# 6_SENSORS.net
KiCad netlist of a schematic drawn in Altium Designer
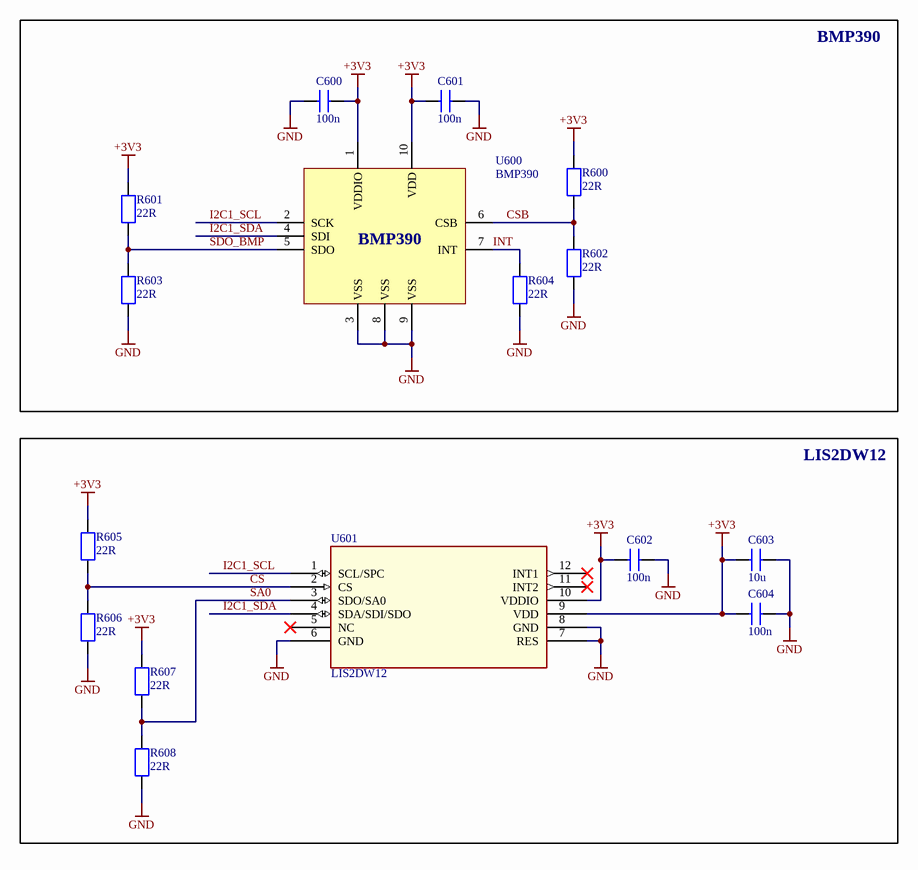
[diagram p0: [6] SENSORS.SchDoc]

(export (version "E")
  (design (tool "Eeschema 10.0.6"))
  (components
    (comp (ref "C600")
      (value "100n")
      (footprint "C0402")
      (description "Multilayer Ceramic Capacitor, 0.1 uF, 25 V, ± 10%, X7R, 0402 [1005 Metric]")
      (fields
        (field (name "MANUFACTURER") "Kyocera AVX")
        (field (name "MANUFACTURER PART NUMBER") "04023C104KAT2A")
      )
      (libsource (lib "ER_SCH_LIB") (part "04023C104KAT2A"))
    )
    (comp (ref "C601")
      (value "100n")
      (footprint "C0402")
      (description "Multilayer Ceramic Capacitor, 0.1 uF, 25 V, ± 10%, X7R, 0402 [1005 Metric]")
      (fields
        (field (name "MANUFACTURER") "Kyocera AVX")
        (field (name "MANUFACTURER PART NUMBER") "04023C104KAT2A")
      )
      (libsource (lib "ER_SCH_LIB") (part "04023C104KAT2A"))
    )
    (comp (ref "C602")
      (value "100n")
      (footprint "C0402")
      (description "Multilayer Ceramic Capacitor, 0.1 uF, 25 V, ± 10%, X7R, 0402 [1005 Metric]")
      (fields
        (field (name "MANUFACTURER") "Kyocera AVX")
        (field (name "MANUFACTURER PART NUMBER") "04023C104KAT2A")
      )
      (libsource (lib "ER_SCH_LIB") (part "04023C104KAT2A"))
    )
    (comp (ref "C603")
      (value "10u")
      (footprint "C0402")
      (description "Capacitor Ceramic Mlcc 0402 10UF 6.3V SMD")
      (fields
        (field (name "MANUFACTURER") "Murata")
        (field (name "MANUFACTURER PART NUMBER") "GRJ155R60J106ME11D")
      )
      (libsource (lib "ER_SCH_LIB") (part "GRJ155R60J106ME11D"))
    )
    (comp (ref "C604")
      (value "100n")
      (footprint "C0402")
      (description "Multilayer Ceramic Capacitor, 0.1 uF, 25 V, ± 10%, X7R, 0402 [1005 Metric]")
      (fields
        (field (name "MANUFACTURER") "Kyocera AVX")
        (field (name "MANUFACTURER PART NUMBER") "04023C104KAT2A")
      )
      (libsource (lib "ER_SCH_LIB") (part "04023C104KAT2A"))
    )
    (comp (ref "R600")
      (value "22R")
      (footprint "R0603")
      (description "SMD Chip Resistor, 22 Ohm, ± 5%, 100 mW, 0603 [1608 Metric], Thick Film, General Purpose")
      (fields
        (field (name "MANUFACTURER") "Yageo")
        (field (name "MANUFACTURER PART NUMBER") "RC0603JR-0722RL")
      )
      (libsource (lib "ER_SCH_LIB") (part "RC0603JR-0722RL"))
    )
    (comp (ref "R601")
      (value "22R")
      (footprint "R0603")
      (description "SMD Chip Resistor, 22 Ohm, ± 5%, 100 mW, 0603 [1608 Metric], Thick Film, General Purpose")
      (fields
        (field (name "MANUFACTURER") "Yageo")
        (field (name "MANUFACTURER PART NUMBER") "RC0603JR-0722RL")
      )
      (libsource (lib "ER_SCH_LIB") (part "RC0603JR-0722RL"))
    )
    (comp (ref "R602")
      (value "22R")
      (footprint "R0603")
      (description "SMD Chip Resistor, 22 Ohm, ± 5%, 100 mW, 0603 [1608 Metric], Thick Film, General Purpose")
      (fields
        (field (name "MANUFACTURER") "Yageo")
        (field (name "MANUFACTURER PART NUMBER") "RC0603JR-0722RL")
      )
      (libsource (lib "ER_SCH_LIB") (part "RC0603JR-0722RL"))
    )
    (comp (ref "R603")
      (value "22R")
      (footprint "R0603")
      (description "SMD Chip Resistor, 22 Ohm, ± 5%, 100 mW, 0603 [1608 Metric], Thick Film, General Purpose")
      (fields
        (field (name "MANUFACTURER") "Yageo")
        (field (name "MANUFACTURER PART NUMBER") "RC0603JR-0722RL")
      )
      (libsource (lib "ER_SCH_LIB") (part "RC0603JR-0722RL"))
    )
    (comp (ref "R604")
      (value "22R")
      (footprint "R0603")
      (description "SMD Chip Resistor, 22 Ohm, ± 5%, 100 mW, 0603 [1608 Metric], Thick Film, General Purpose")
      (fields
        (field (name "MANUFACTURER") "Yageo")
        (field (name "MANUFACTURER PART NUMBER") "RC0603JR-0722RL")
      )
      (libsource (lib "ER_SCH_LIB") (part "RC0603JR-0722RL"))
    )
    (comp (ref "R605")
      (value "22R")
      (footprint "R0603")
      (description "SMD Chip Resistor, 22 Ohm, ± 5%, 100 mW, 0603 [1608 Metric], Thick Film, General Purpose")
      (fields
        (field (name "MANUFACTURER") "Yageo")
        (field (name "MANUFACTURER PART NUMBER") "RC0603JR-0722RL")
      )
      (libsource (lib "ER_SCH_LIB") (part "RC0603JR-0722RL"))
    )
    (comp (ref "R606")
      (value "22R")
      (footprint "R0603")
      (description "SMD Chip Resistor, 22 Ohm, ± 5%, 100 mW, 0603 [1608 Metric], Thick Film, General Purpose")
      (fields
        (field (name "MANUFACTURER") "Yageo")
        (field (name "MANUFACTURER PART NUMBER") "RC0603JR-0722RL")
      )
      (libsource (lib "ER_SCH_LIB") (part "RC0603JR-0722RL"))
    )
    (comp (ref "R607")
      (value "22R")
      (footprint "R0603")
      (description "SMD Chip Resistor, 22 Ohm, ± 5%, 100 mW, 0603 [1608 Metric], Thick Film, General Purpose")
      (fields
        (field (name "MANUFACTURER") "Yageo")
        (field (name "MANUFACTURER PART NUMBER") "RC0603JR-0722RL")
      )
      (libsource (lib "ER_SCH_LIB") (part "RC0603JR-0722RL"))
    )
    (comp (ref "R608")
      (value "22R")
      (footprint "R0603")
      (description "SMD Chip Resistor, 22 Ohm, ± 5%, 100 mW, 0603 [1608 Metric], Thick Film, General Purpose")
      (fields
        (field (name "MANUFACTURER") "Yageo")
        (field (name "MANUFACTURER PART NUMBER") "RC0603JR-0722RL")
      )
      (libsource (lib "ER_SCH_LIB") (part "RC0603JR-0722RL"))
    )
    (comp (ref "U600")
      (value "BMP390")
      (footprint "LGA10")
      (description "Pressure sensor, 300-1250hPa, 2.0*2.0*0.75mm, I2C/SPI")
      (fields (field (name "MANUFACTURER") "Bosch Sensortec"))
      (libsource (lib "ER_SCH_LIB") (part "BMP390"))
    )
    (comp (ref "U601")
      (value "LIS2DW12")
      (footprint "LGA12")
      (description "LIS2DW12 Series 3 Axis ±2/±4/±8/±16g 3-Axis \"Femto\" Accelerometer - LGA-12")
      (fields
        (field (name "MANUFACTURER") "STMicroelectronics")
        (field (name "MANUFACTURER PART NUMBER") "LIS2DW12TR")
      )
      (libsource (lib "ER_SCH_LIB") (part "LIS2DW12TR"))
    )
  )
  (nets
    (net (code "1") (name "+3V3") (class "Default")
      (node (ref "C600") (pin "1") (pinfunction "1_1") (pintype "passive"))
      (node (ref "C601") (pin "2") (pinfunction "2_2") (pintype "passive"))
      (node (ref "C602") (pin "2") (pinfunction "2_2") (pintype "passive"))
      (node (ref "C603") (pin "2") (pinfunction "2_2") (pintype "passive"))
      (node (ref "C604") (pin "2") (pinfunction "2_2") (pintype "passive"))
      (node (ref "R600") (pin "2") (pinfunction "2_2") (pintype "passive"))
      (node (ref "R601") (pin "2") (pinfunction "2_2") (pintype "passive"))
      (node (ref "R605") (pin "2") (pinfunction "2_2") (pintype "passive"))
      (node (ref "R607") (pin "2") (pinfunction "2_2") (pintype "passive"))
      (node (ref "U600") (pin "1") (pinfunction "VDDIO_1") (pintype "passive"))
      (node (ref "U600") (pin "10") (pinfunction "VDD_10") (pintype "passive"))
      (node (ref "U601") (pin "10") (pinfunction "VDDIO_10") (pintype "power_in"))
      (node (ref "U601") (pin "9") (pinfunction "VDD_9") (pintype "power_in"))
    )
    (net (code "2") (name "/CS") (class "Default")
      (node (ref "R605") (pin "1") (pinfunction "1_1") (pintype "passive"))
      (node (ref "R606") (pin "2") (pinfunction "2_2") (pintype "passive"))
      (node (ref "U601") (pin "2") (pinfunction "CS_2") (pintype "input"))
    )
    (net (code "3") (name "/CSB") (class "Default")
      (node (ref "R600") (pin "1") (pinfunction "1_1") (pintype "passive"))
      (node (ref "R602") (pin "2") (pinfunction "2_2") (pintype "passive"))
      (node (ref "U600") (pin "6") (pinfunction "CSB_6") (pintype "passive"))
    )
    (net (code "4") (name "/I2C1_SCL") (class "Default")
      (node (ref "U600") (pin "2") (pinfunction "SCK_2") (pintype "passive"))
      (node (ref "U601") (pin "1") (pinfunction "SCL/SPC_1") (pintype "bidirectional"))
    )
    (net (code "5") (name "/I2C1_SDA") (class "Default")
      (node (ref "U600") (pin "4") (pinfunction "SDI_4") (pintype "passive"))
      (node (ref "U601") (pin "4") (pinfunction "SDA/SDI/SDO_4") (pintype "bidirectional"))
    )
    (net (code "6") (name "/INT") (class "Default")
      (node (ref "R604") (pin "2") (pinfunction "2_2") (pintype "passive"))
      (node (ref "U600") (pin "7") (pinfunction "INT_7") (pintype "passive"))
    )
    (net (code "7") (name "/SA0") (class "Default")
      (node (ref "R607") (pin "1") (pinfunction "1_1") (pintype "passive"))
      (node (ref "R608") (pin "2") (pinfunction "2_2") (pintype "passive"))
      (node (ref "U601") (pin "3") (pinfunction "SDO/SA0_3") (pintype "bidirectional"))
    )
    (net (code "8") (name "/SDO_BMP") (class "Default")
      (node (ref "R601") (pin "1") (pinfunction "1_1") (pintype "passive"))
      (node (ref "R603") (pin "2") (pinfunction "2_2") (pintype "passive"))
      (node (ref "U600") (pin "5") (pinfunction "SDO_5") (pintype "passive"))
    )
    (net (code "9") (name "GND") (class "Default")
      (node (ref "C600") (pin "2") (pinfunction "2_2") (pintype "passive"))
      (node (ref "C601") (pin "1") (pinfunction "1_1") (pintype "passive"))
      (node (ref "C602") (pin "1") (pinfunction "1_1") (pintype "passive"))
      (node (ref "C603") (pin "1") (pinfunction "1_1") (pintype "passive"))
      (node (ref "C604") (pin "1") (pinfunction "1_1") (pintype "passive"))
      (node (ref "R602") (pin "1") (pinfunction "1_1") (pintype "passive"))
      (node (ref "R603") (pin "1") (pinfunction "1_1") (pintype "passive"))
      (node (ref "R604") (pin "1") (pinfunction "1_1") (pintype "passive"))
      (node (ref "R606") (pin "1") (pinfunction "1_1") (pintype "passive"))
      (node (ref "R608") (pin "1") (pinfunction "1_1") (pintype "passive"))
      (node (ref "U600") (pin "3") (pinfunction "VSS_3") (pintype "passive"))
      (node (ref "U600") (pin "8") (pinfunction "VSS_8") (pintype "passive"))
      (node (ref "U600") (pin "9") (pinfunction "VSS_9") (pintype "passive"))
      (node (ref "U601") (pin "6") (pinfunction "GND_6") (pintype "passive"))
      (node (ref "U601") (pin "7") (pinfunction "RES_7") (pintype "passive"))
      (node (ref "U601") (pin "8") (pinfunction "GND_8") (pintype "passive"))
    )
    (net (code "10") (name "unconnected-(U601-INT1-Pad12)") (class "Default")
      (node (ref "U601") (pin "12") (pinfunction "INT1_12") (pintype "output+no_connect"))
    )
    (net (code "11") (name "unconnected-(U601-INT2-Pad11)") (class "Default")
      (node (ref "U601") (pin "11") (pinfunction "INT2_11") (pintype "output+no_connect"))
    )
    (net (code "12") (name "unconnected-(U601-NC-Pad5)") (class "Default")
      (node (ref "U601") (pin "5") (pinfunction "NC_5") (pintype "passive+no_connect"))
    )
  )
)
